# quantum_PSU_V2.net
KiCad netlist of a schematic drawn in EAGLE
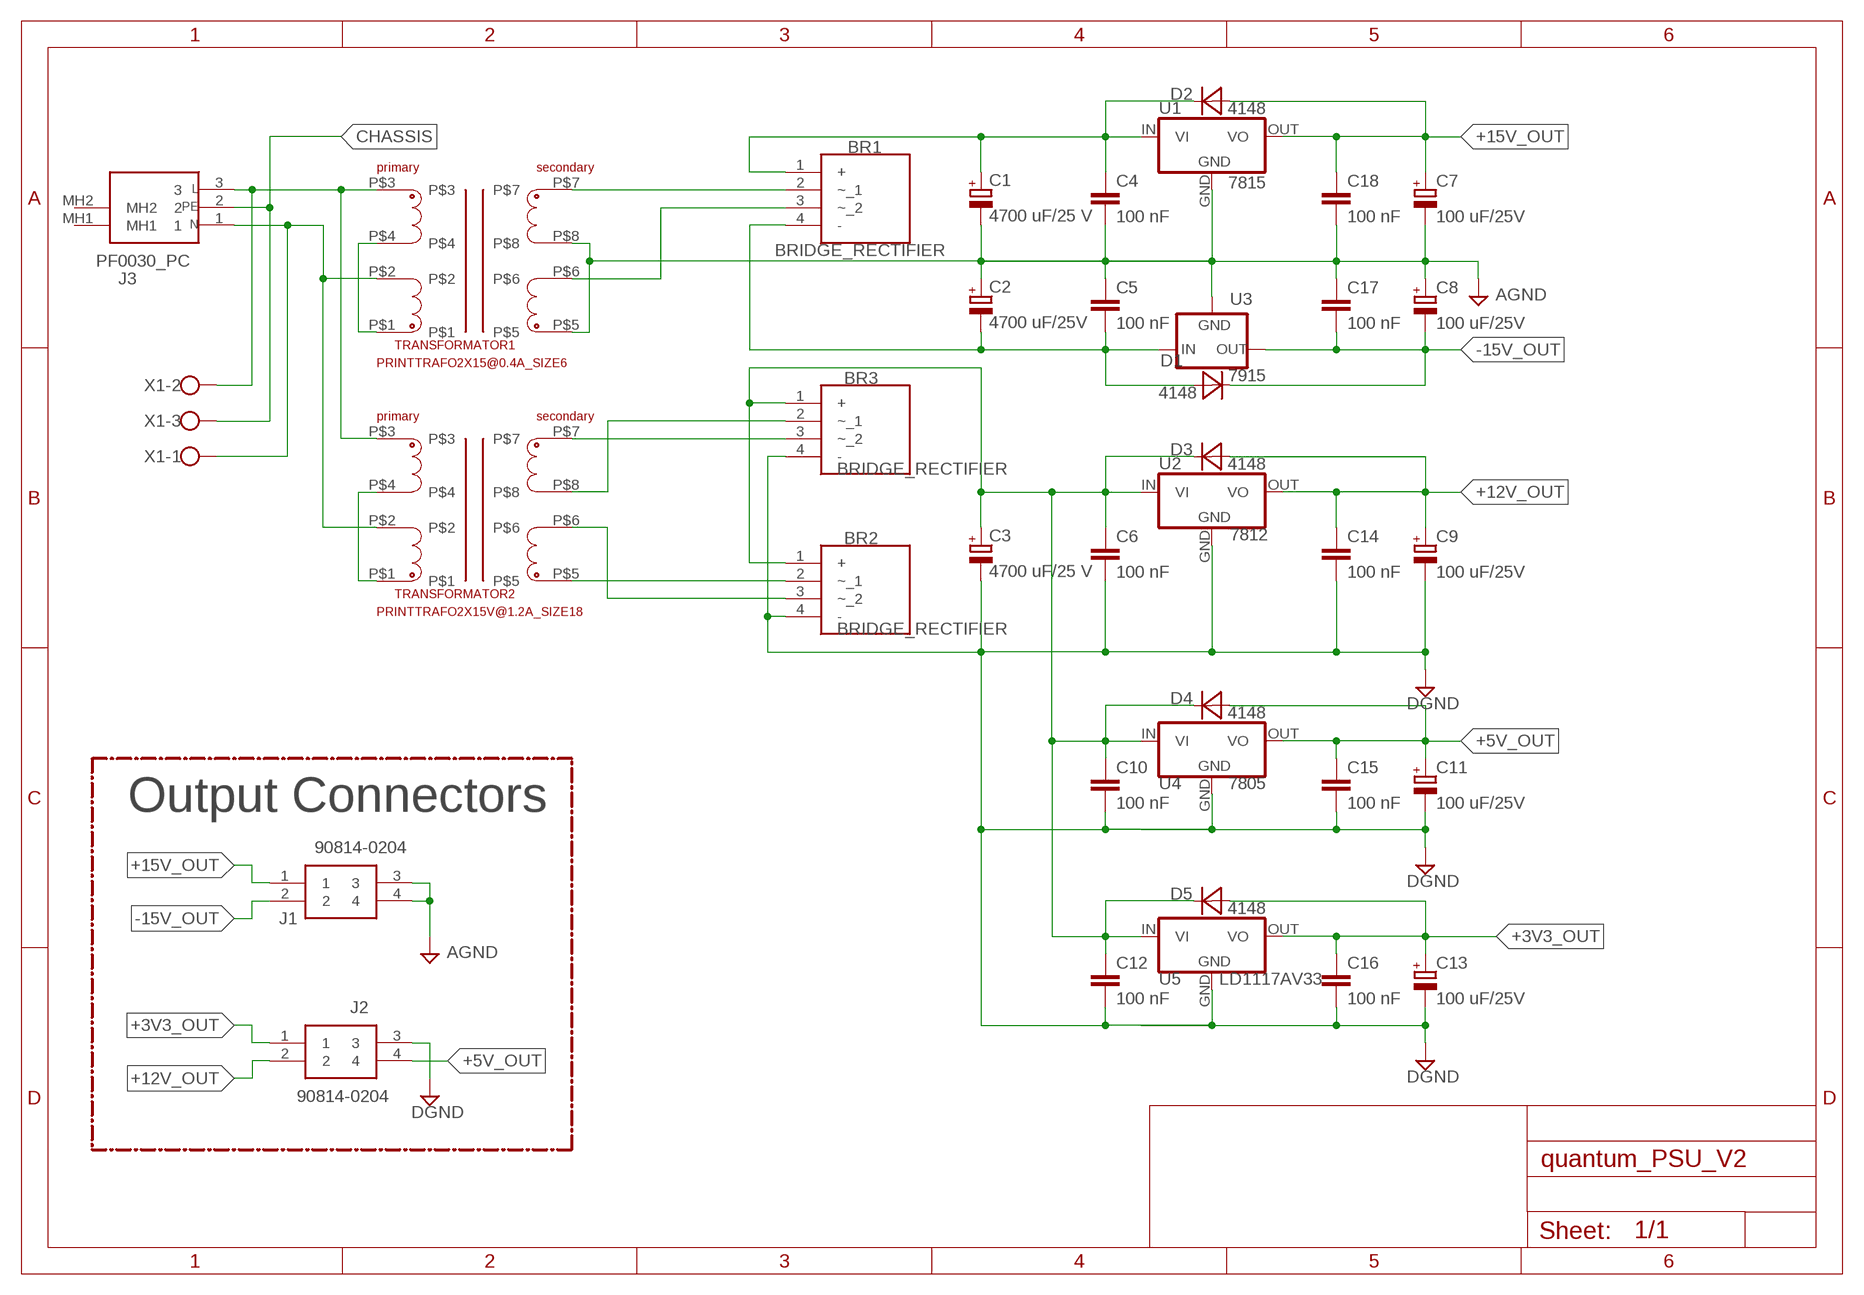
[diagram p0: schematic, sheet 1]

(export (version "E")
  (design (tool "Eeschema 10.0.6"))
  (components
    (comp (ref "BR1")
      (value "BRIDGE_RECTIFIER")
      (footprint "eagle-import:KBP308G")
      (fields
        (field (name "MANUFACTURER_PART_NUMBER") "KBP308G")
        (field (name "MOUSER_PART_NUMBER") "621-KBP308G")
      )
      (libsource (lib "eagle-import") (part "BRIDGE_RECTIFIER"))
    )
    (comp (ref "BR2")
      (value "BRIDGE_RECTIFIER")
      (footprint "eagle-import:KBP308G")
      (fields
        (field (name "MANUFACTURER_PART_NUMBER") "KBP308G")
        (field (name "MOUSER_PART_NUMBER") "621-KBP308G")
      )
      (libsource (lib "eagle-import") (part "BRIDGE_RECTIFIER"))
    )
    (comp (ref "BR3")
      (value "BRIDGE_RECTIFIER")
      (footprint "eagle-import:KBP308G")
      (fields
        (field (name "MANUFACTURER_PART_NUMBER") "KBP308G")
        (field (name "MOUSER_PART_NUMBER") "621-KBP308G")
      )
      (libsource (lib "eagle-import") (part "BRIDGE_RECTIFIER"))
    )
    (comp (ref "C1")
      (value "4700 uF/25 V")
      (footprint "eagle-import:ELECTROLYTIC_16MM")
      (libsource (lib "eagle-import") (part "CAPACITOR_ELECTROLYTIC_16MM-THT"))
    )
    (comp (ref "C2")
      (value "4700 uF/25V")
      (footprint "eagle-import:ELECTROLYTIC_16MM")
      (libsource (lib "eagle-import") (part "CAPACITOR_ELECTROLYTIC_16MM-THT"))
    )
    (comp (ref "C3")
      (value "4700 uF/25 V")
      (footprint "eagle-import:ELECTROLYTIC_16MM")
      (libsource (lib "eagle-import") (part "CAPACITOR_ELECTROLYTIC_16MM-THT"))
    )
    (comp (ref "C4")
      (value "100 nF")
      (footprint "eagle-import:C5MM")
      (libsource (lib "eagle-import") (part "CAPACITOR_5MM"))
    )
    (comp (ref "C5")
      (value "100 nF")
      (footprint "eagle-import:C5MM")
      (libsource (lib "eagle-import") (part "CAPACITOR_5MM"))
    )
    (comp (ref "C6")
      (value "100 nF")
      (footprint "eagle-import:C5MM")
      (libsource (lib "eagle-import") (part "CAPACITOR_5MM"))
    )
    (comp (ref "C7")
      (value "100 uF/25V")
      (footprint "eagle-import:ELECTROLYTIC_8MM")
      (libsource (lib "eagle-import") (part "CAPACITOR_ELECTROLYTIC_8MM-THT"))
    )
    (comp (ref "C8")
      (value "100 uF/25V")
      (footprint "eagle-import:ELECTROLYTIC_8MM")
      (libsource (lib "eagle-import") (part "CAPACITOR_ELECTROLYTIC_8MM-THT"))
    )
    (comp (ref "C9")
      (value "100 uF/25V")
      (footprint "eagle-import:ELECTROLYTIC_8MM")
      (libsource (lib "eagle-import") (part "CAPACITOR_ELECTROLYTIC_8MM-THT"))
    )
    (comp (ref "C10")
      (value "100 nF")
      (footprint "eagle-import:C5MM")
      (libsource (lib "eagle-import") (part "CAPACITOR_5MM"))
    )
    (comp (ref "C11")
      (value "100 uF/25V")
      (footprint "eagle-import:ELECTROLYTIC_8MM")
      (libsource (lib "eagle-import") (part "CAPACITOR_ELECTROLYTIC_8MM-THT"))
    )
    (comp (ref "C12")
      (value "100 nF")
      (footprint "eagle-import:C5MM")
      (libsource (lib "eagle-import") (part "CAPACITOR_5MM"))
    )
    (comp (ref "C13")
      (value "100 uF/25V")
      (footprint "eagle-import:ELECTROLYTIC_8MM")
      (libsource (lib "eagle-import") (part "CAPACITOR_ELECTROLYTIC_8MM-THT"))
    )
    (comp (ref "C14")
      (value "100 nF")
      (footprint "eagle-import:C5MM")
      (libsource (lib "eagle-import") (part "CAPACITOR_5MM"))
    )
    (comp (ref "C15")
      (value "100 nF")
      (footprint "eagle-import:C5MM")
      (libsource (lib "eagle-import") (part "CAPACITOR_5MM"))
    )
    (comp (ref "C16")
      (value "100 nF")
      (footprint "eagle-import:C5MM")
      (libsource (lib "eagle-import") (part "CAPACITOR_5MM"))
    )
    (comp (ref "C17")
      (value "100 nF")
      (footprint "eagle-import:C5MM")
      (libsource (lib "eagle-import") (part "CAPACITOR_5MM"))
    )
    (comp (ref "C18")
      (value "100 nF")
      (footprint "eagle-import:C5MM")
      (libsource (lib "eagle-import") (part "CAPACITOR_5MM"))
    )
    (comp (ref "D1")
      (value "4148")
      (footprint "eagle-import:DIODE_THT_STANDING")
      (fields (field (name "MOUSER_PART_NUMBER") "..."))
      (libsource (lib "eagle-import") (part "DIODE_4148_THT"))
    )
    (comp (ref "D2")
      (value "4148")
      (footprint "eagle-import:DIODE_THT_STANDING")
      (fields (field (name "MOUSER_PART_NUMBER") "..."))
      (libsource (lib "eagle-import") (part "DIODE_4148_THT"))
    )
    (comp (ref "D3")
      (value "4148")
      (footprint "eagle-import:DIODE_THT_STANDING")
      (fields (field (name "MOUSER_PART_NUMBER") "..."))
      (libsource (lib "eagle-import") (part "DIODE_4148_THT"))
    )
    (comp (ref "D4")
      (value "4148")
      (footprint "eagle-import:DIODE_THT_STANDING")
      (fields (field (name "MOUSER_PART_NUMBER") "..."))
      (libsource (lib "eagle-import") (part "DIODE_4148_THT"))
    )
    (comp (ref "D5")
      (value "4148")
      (footprint "eagle-import:DIODE_THT_STANDING")
      (fields (field (name "MOUSER_PART_NUMBER") "..."))
      (libsource (lib "eagle-import") (part "DIODE_4148_THT"))
    )
    (comp (ref "J1")
      (value "90814-0204")
      (footprint "eagle-import:MOLEX_90814-0204")
      (fields (field (name "MOUSER_PART_NUMBER") "538-90814-0204"))
      (libsource (lib "eagle-import") (part "90814-0204"))
    )
    (comp (ref "J2")
      (value "90814-0204")
      (footprint "eagle-import:MOLEX_90814-0204")
      (fields (field (name "MOUSER_PART_NUMBER") "538-90814-0204"))
      (libsource (lib "eagle-import") (part "90814-0204"))
    )
    (comp (ref "J3")
      (value "PF0030_PC")
      (footprint "eagle-import:PF0030PC")
      (fields
        (field (name "MANUFACTURER_PART_NUMBER") "PF0030/PC")
        (field (name "MOUSER_PART_NUMBER") "161-PF0030/PC")
      )
      (libsource (lib "eagle-import") (part "PF0030_PC"))
    )
    (comp (ref "TRANSFORMATOR1")
      (value "PRINTTRAFO2X15@0.4A_SIZE6")
      (footprint "eagle-import:LP_SIZE_6")
      (fields (field (name "MOUSER_PART_NUMBER") "530-LP-30-200"))
      (libsource (lib "eagle-import") (part "PRINTTRAFO_SIZE62X15@0.4A"))
    )
    (comp (ref "TRANSFORMATOR2")
      (value "PRINTTRAFO2X15V@1.2A_SIZE18")
      (footprint "eagle-import:LPI_SIZE_18")
      (fields (field (name "MOUSER_PART_NUMBER") "530-30-600-LPI"))
      (libsource (lib "eagle-import") (part "PRINTTRAFO_SIZE182X15V@1.2A"))
    )
    (comp (ref "U1")
      (value "7815")
      (footprint "eagle-import:78XXS_")
      (libsource (lib "eagle-import") (part "78_THT"))
    )
    (comp (ref "U2")
      (value "7812")
      (footprint "eagle-import:78XXS_")
      (libsource (lib "eagle-import") (part "78_THT"))
    )
    (comp (ref "U3")
      (value "7915")
      (footprint "eagle-import:79XXS")
      (libsource (lib "eagle-import") (part "79_THT"))
    )
    (comp (ref "U4")
      (value "7805")
      (footprint "eagle-import:78XXS_")
      (libsource (lib "eagle-import") (part "78_THT"))
    )
    (comp (ref "U5")
      (value "LD1117AV33")
      (footprint "eagle-import:78XXS_")
      (libsource (lib "eagle-import") (part "78_THT"))
    )
    (comp (ref "X1")
      (value "CONNECTOR_3POL")
      (footprint "eagle-import:W237-103")
      (libsource (lib "eagle-import") (part "CONNECTOR_3POL"))
    )
  )
  (nets
    (net (code "1") (name "+3V3_OUT") (class "Default")
      (node (ref "C13") (pin "+") (pinfunction "+_+") (pintype "passive"))
      (node (ref "C16") (pin "1") (pinfunction "1_1") (pintype "passive"))
      (node (ref "D5") (pin "A") (pinfunction "A_A") (pintype "passive"))
      (node (ref "J2") (pin "1") (pinfunction "1_1") (pintype "bidirectional"))
      (node (ref "U5") (pin "OUT") (pinfunction "VO_OUT") (pintype "passive"))
    )
    (net (code "2") (name "+5V_OUT") (class "Default")
      (node (ref "C11") (pin "+") (pinfunction "+_+") (pintype "passive"))
      (node (ref "C15") (pin "1") (pinfunction "1_1") (pintype "passive"))
      (node (ref "D4") (pin "A") (pinfunction "A_A") (pintype "passive"))
      (node (ref "J2") (pin "4") (pinfunction "4_4") (pintype "bidirectional"))
      (node (ref "U4") (pin "OUT") (pinfunction "VO_OUT") (pintype "passive"))
    )
    (net (code "3") (name "+12V_OUT") (class "Default")
      (node (ref "C14") (pin "1") (pinfunction "1_1") (pintype "passive"))
      (node (ref "C9") (pin "+") (pinfunction "+_+") (pintype "passive"))
      (node (ref "D3") (pin "A") (pinfunction "A_A") (pintype "passive"))
      (node (ref "J2") (pin "2") (pinfunction "2_2") (pintype "bidirectional"))
      (node (ref "U2") (pin "OUT") (pinfunction "VO_OUT") (pintype "passive"))
    )
    (net (code "4") (name "+15V_OUT") (class "Default")
      (node (ref "C18") (pin "1") (pinfunction "1_1") (pintype "passive"))
      (node (ref "C7") (pin "+") (pinfunction "+_+") (pintype "passive"))
      (node (ref "D2") (pin "A") (pinfunction "A_A") (pintype "passive"))
      (node (ref "J1") (pin "1") (pinfunction "1_1") (pintype "bidirectional"))
      (node (ref "U1") (pin "OUT") (pinfunction "VO_OUT") (pintype "passive"))
    )
    (net (code "5") (name "-15V_OUT") (class "Default")
      (node (ref "C17") (pin "2") (pinfunction "2_2") (pintype "passive"))
      (node (ref "C8") (pin "-") (pinfunction "-_-") (pintype "passive"))
      (node (ref "D1") (pin "C") (pinfunction "C_C") (pintype "passive"))
      (node (ref "J1") (pin "2") (pinfunction "2_2") (pintype "bidirectional"))
      (node (ref "U3") (pin "OUT") (pinfunction "OUT_OUT") (pintype "passive"))
    )
    (net (code "6") (name "AGND") (class "Default")
      (node (ref "C1") (pin "-") (pinfunction "-_-") (pintype "passive"))
      (node (ref "C17") (pin "1") (pinfunction "1_1") (pintype "passive"))
      (node (ref "C18") (pin "2") (pinfunction "2_2") (pintype "passive"))
      (node (ref "C2") (pin "+") (pinfunction "+_+") (pintype "passive"))
      (node (ref "C4") (pin "2") (pinfunction "2_2") (pintype "passive"))
      (node (ref "C5") (pin "1") (pinfunction "1_1") (pintype "passive"))
      (node (ref "C7") (pin "-") (pinfunction "-_-") (pintype "passive"))
      (node (ref "C8") (pin "+") (pinfunction "+_+") (pintype "passive"))
      (node (ref "J1") (pin "3") (pinfunction "3_3") (pintype "bidirectional"))
      (node (ref "J1") (pin "4") (pinfunction "4_4") (pintype "bidirectional"))
      (node (ref "TRANSFORMATOR1") (pin "P$5") (pinfunction "P$5_P$5") (pintype "bidirectional"))
      (node (ref "TRANSFORMATOR1") (pin "P$8") (pinfunction "P$8_P$8") (pintype "bidirectional"))
      (node (ref "U1") (pin "GND") (pinfunction "GND_GND") (pintype "passive"))
      (node (ref "U3") (pin "GND") (pinfunction "GND_GND") (pintype "input"))
    )
    (net (code "7") (name "CHASSIS") (class "Default")
      (node (ref "J3") (pin "2") (pinfunction "2_2") (pintype "bidirectional"))
      (node (ref "X1") (pin "3") (pinfunction "KL_3") (pintype "passive"))
    )
    (net (code "8") (name "DGND") (class "Default")
      (node (ref "BR2") (pin "4") (pinfunction "-_4") (pintype "bidirectional"))
      (node (ref "BR3") (pin "4") (pinfunction "-_4") (pintype "bidirectional"))
      (node (ref "C10") (pin "2") (pinfunction "2_2") (pintype "passive"))
      (node (ref "C11") (pin "-") (pinfunction "-_-") (pintype "passive"))
      (node (ref "C12") (pin "2") (pinfunction "2_2") (pintype "passive"))
      (node (ref "C13") (pin "-") (pinfunction "-_-") (pintype "passive"))
      (node (ref "C14") (pin "2") (pinfunction "2_2") (pintype "passive"))
      (node (ref "C15") (pin "2") (pinfunction "2_2") (pintype "passive"))
      (node (ref "C16") (pin "2") (pinfunction "2_2") (pintype "passive"))
      (node (ref "C3") (pin "-") (pinfunction "-_-") (pintype "passive"))
      (node (ref "C6") (pin "2") (pinfunction "2_2") (pintype "passive"))
      (node (ref "C9") (pin "-") (pinfunction "-_-") (pintype "passive"))
      (node (ref "J2") (pin "3") (pinfunction "3_3") (pintype "bidirectional"))
      (node (ref "U2") (pin "GND") (pinfunction "GND_GND") (pintype "passive"))
      (node (ref "U4") (pin "GND") (pinfunction "GND_GND") (pintype "passive"))
      (node (ref "U5") (pin "GND") (pinfunction "GND_GND") (pintype "passive"))
    )
    (net (code "9") (name "Net-(BR1-+)") (class "Default")
      (node (ref "BR1") (pin "1") (pinfunction "+_1") (pintype "bidirectional"))
      (node (ref "C1") (pin "+") (pinfunction "+_+") (pintype "passive"))
      (node (ref "C4") (pin "1") (pinfunction "1_1") (pintype "passive"))
      (node (ref "D2") (pin "C") (pinfunction "C_C") (pintype "passive"))
      (node (ref "U1") (pin "IN") (pinfunction "VI_IN") (pintype "input"))
    )
    (net (code "10") (name "Net-(BR1--)") (class "Default")
      (node (ref "BR1") (pin "4") (pinfunction "-_4") (pintype "bidirectional"))
      (node (ref "C2") (pin "-") (pinfunction "-_-") (pintype "passive"))
      (node (ref "C5") (pin "2") (pinfunction "2_2") (pintype "passive"))
      (node (ref "D1") (pin "A") (pinfunction "A_A") (pintype "passive"))
      (node (ref "U3") (pin "IN") (pinfunction "IN_IN") (pintype "input"))
    )
    (net (code "11") (name "Net-(BR1-~{_1})") (class "Default")
      (node (ref "BR1") (pin "2") (pinfunction "~{_1}_2") (pintype "bidirectional"))
      (node (ref "TRANSFORMATOR1") (pin "P$7") (pinfunction "P$7_P$7") (pintype "bidirectional"))
    )
    (net (code "12") (name "Net-(BR1-~{_2})") (class "Default")
      (node (ref "BR1") (pin "3") (pinfunction "~{_2}_3") (pintype "bidirectional"))
      (node (ref "TRANSFORMATOR1") (pin "P$6") (pinfunction "P$6_P$6") (pintype "bidirectional"))
    )
    (net (code "13") (name "Net-(BR2-+)") (class "Default")
      (node (ref "BR2") (pin "1") (pinfunction "+_1") (pintype "bidirectional"))
      (node (ref "BR3") (pin "1") (pinfunction "+_1") (pintype "bidirectional"))
      (node (ref "C10") (pin "1") (pinfunction "1_1") (pintype "passive"))
      (node (ref "C12") (pin "1") (pinfunction "1_1") (pintype "passive"))
      (node (ref "C3") (pin "+") (pinfunction "+_+") (pintype "passive"))
      (node (ref "C6") (pin "1") (pinfunction "1_1") (pintype "passive"))
      (node (ref "D3") (pin "C") (pinfunction "C_C") (pintype "passive"))
      (node (ref "D4") (pin "C") (pinfunction "C_C") (pintype "passive"))
      (node (ref "D5") (pin "C") (pinfunction "C_C") (pintype "passive"))
      (node (ref "U2") (pin "IN") (pinfunction "VI_IN") (pintype "input"))
      (node (ref "U4") (pin "IN") (pinfunction "VI_IN") (pintype "input"))
      (node (ref "U5") (pin "IN") (pinfunction "VI_IN") (pintype "input"))
    )
    (net (code "14") (name "Net-(BR2-~{_1})") (class "Default")
      (node (ref "BR2") (pin "2") (pinfunction "~{_1}_2") (pintype "bidirectional"))
      (node (ref "TRANSFORMATOR2") (pin "P$5") (pinfunction "P$5_P$5") (pintype "bidirectional"))
    )
    (net (code "15") (name "Net-(BR2-~{_2})") (class "Default")
      (node (ref "BR2") (pin "3") (pinfunction "~{_2}_3") (pintype "bidirectional"))
      (node (ref "TRANSFORMATOR2") (pin "P$6") (pinfunction "P$6_P$6") (pintype "bidirectional"))
    )
    (net (code "16") (name "Net-(BR3-~{_1})") (class "Default")
      (node (ref "BR3") (pin "2") (pinfunction "~{_1}_2") (pintype "bidirectional"))
      (node (ref "TRANSFORMATOR2") (pin "P$8") (pinfunction "P$8_P$8") (pintype "bidirectional"))
    )
    (net (code "17") (name "Net-(BR3-~{_2})") (class "Default")
      (node (ref "BR3") (pin "3") (pinfunction "~{_2}_3") (pintype "bidirectional"))
      (node (ref "TRANSFORMATOR2") (pin "P$7") (pinfunction "P$7_P$7") (pintype "bidirectional"))
    )
    (net (code "18") (name "Net-(TRANSFORMATOR1-PadP$1)") (class "Default")
      (node (ref "TRANSFORMATOR1") (pin "P$1") (pinfunction "P$1_P$1") (pintype "bidirectional"))
      (node (ref "TRANSFORMATOR1") (pin "P$4") (pinfunction "P$4_P$4") (pintype "bidirectional"))
    )
    (net (code "19") (name "Net-(TRANSFORMATOR2-PadP$1)") (class "Default")
      (node (ref "TRANSFORMATOR2") (pin "P$1") (pinfunction "P$1_P$1") (pintype "bidirectional"))
      (node (ref "TRANSFORMATOR2") (pin "P$4") (pinfunction "P$4_P$4") (pintype "bidirectional"))
    )
    (net (code "20") (name "Net-(X1A-KL)") (class "Default")
      (node (ref "J3") (pin "1") (pinfunction "1_1") (pintype "bidirectional"))
      (node (ref "TRANSFORMATOR1") (pin "P$2") (pinfunction "P$2_P$2") (pintype "bidirectional"))
      (node (ref "TRANSFORMATOR2") (pin "P$2") (pinfunction "P$2_P$2") (pintype "bidirectional"))
      (node (ref "X1") (pin "1") (pinfunction "KL_1") (pintype "passive"))
    )
    (net (code "21") (name "Net-(X1B-KL)") (class "Default")
      (node (ref "J3") (pin "3") (pinfunction "3_3") (pintype "bidirectional"))
      (node (ref "TRANSFORMATOR1") (pin "P$3") (pinfunction "P$3_P$3") (pintype "bidirectional"))
      (node (ref "TRANSFORMATOR2") (pin "P$3") (pinfunction "P$3_P$3") (pintype "bidirectional"))
      (node (ref "X1") (pin "2") (pinfunction "KL_2") (pintype "passive"))
    )
    (net (code "22") (name "unconnected-(J3-PadMH1)") (class "Default")
      (node (ref "J3") (pin "MH1") (pinfunction "MH1_MH1") (pintype "bidirectional"))
    )
    (net (code "23") (name "unconnected-(J3-PadMH2)") (class "Default")
      (node (ref "J3") (pin "MH2") (pinfunction "MH2_MH2") (pintype "bidirectional"))
    )
  )
)
